# TPM2_0.net
KiCad netlist of a schematic drawn in EAGLE
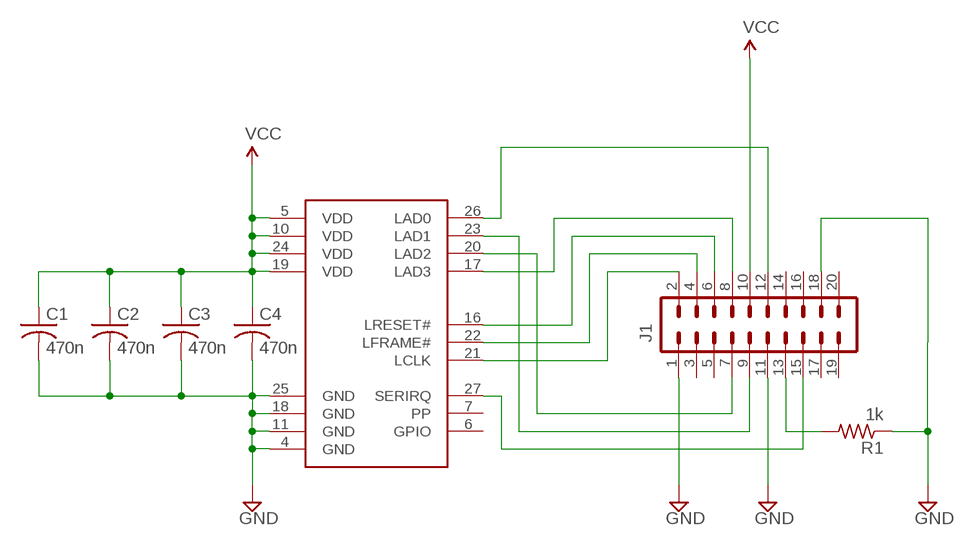
[diagram p0: schematic, sheet 1]

(export (version "E")
  (design (tool "Eeschema 10.0.6"))
  (components
    (comp (ref "C1")
      (value "470n")
      (footprint "eagle-import:C0805K")
      (libsource (lib "eagle-import") (part "C-USC0805K"))
    )
    (comp (ref "C2")
      (value "470n")
      (footprint "eagle-import:C0805K")
      (libsource (lib "eagle-import") (part "C-USC0805K"))
    )
    (comp (ref "C3")
      (value "470n")
      (footprint "eagle-import:C0805K")
      (libsource (lib "eagle-import") (part "C-USC0805K"))
    )
    (comp (ref "C4")
      (value "470n")
      (footprint "eagle-import:C0805K")
      (libsource (lib "eagle-import") (part "C-USC0805K"))
    )
    (comp (ref "J1")
      (value "M10X22X10_LOCK")
      (footprint "eagle-import:2X10_LOCK")
      (libsource (lib "eagle-import") (part "M10X22X10_LOCK"))
    )
    (comp (ref "R1")
      (value "1k")
      (footprint "eagle-import:R0805")
      (libsource (lib "eagle-import") (part "R-US_R0805"))
    )
    (comp (ref "U$1")
      (value "SLB9965")
      (footprint "eagle-import:INF-PG-TSSOP-28-16_M_1PRIMARY")
      (libsource (lib "eagle-import") (part "SLB9965"))
    )
  )
  (nets
    (net (code "1") (name "GND") (class "Default")
      (node (ref "C1") (pin "2") (pinfunction "2_2") (pintype "passive"))
      (node (ref "C2") (pin "2") (pinfunction "2_2") (pintype "passive"))
      (node (ref "C3") (pin "2") (pinfunction "2_2") (pintype "passive"))
      (node (ref "C4") (pin "2") (pinfunction "2_2") (pintype "passive"))
      (node (ref "J1") (pin "1") (pinfunction "1_1") (pintype "passive"))
      (node (ref "J1") (pin "11") (pinfunction "11_11") (pintype "passive"))
      (node (ref "J1") (pin "18") (pinfunction "18_18") (pintype "passive"))
      (node (ref "R1") (pin "1") (pinfunction "1_1") (pintype "passive"))
      (node (ref "U$1") (pin "11") (pinfunction "GND_11") (pintype "power_in"))
      (node (ref "U$1") (pin "18") (pinfunction "GND_18") (pintype "power_in"))
      (node (ref "U$1") (pin "25") (pinfunction "GND_25") (pintype "power_in"))
      (node (ref "U$1") (pin "4") (pinfunction "GND_4") (pintype "power_in"))
    )
    (net (code "2") (name "Net-(J1-Pad13)") (class "Default")
      (node (ref "J1") (pin "13") (pinfunction "13_13") (pintype "passive"))
      (node (ref "R1") (pin "2") (pinfunction "2_2") (pintype "passive"))
    )
    (net (code "3") (name "Net-(U$1-LAD0)") (class "Default")
      (node (ref "J1") (pin "12") (pinfunction "12_12") (pintype "passive"))
      (node (ref "U$1") (pin "26") (pinfunction "LAD0_26") (pintype "bidirectional"))
    )
    (net (code "4") (name "Net-(U$1-LAD1)") (class "Default")
      (node (ref "J1") (pin "9") (pinfunction "9_9") (pintype "passive"))
      (node (ref "U$1") (pin "23") (pinfunction "LAD1_23") (pintype "bidirectional"))
    )
    (net (code "5") (name "Net-(U$1-LAD2)") (class "Default")
      (node (ref "J1") (pin "7") (pinfunction "7_7") (pintype "passive"))
      (node (ref "U$1") (pin "20") (pinfunction "LAD2_20") (pintype "bidirectional"))
    )
    (net (code "6") (name "Net-(U$1-LAD3)") (class "Default")
      (node (ref "J1") (pin "8") (pinfunction "8_8") (pintype "passive"))
      (node (ref "U$1") (pin "17") (pinfunction "LAD3_17") (pintype "bidirectional"))
    )
    (net (code "7") (name "Net-(U$1-LCLK)") (class "Default")
      (node (ref "J1") (pin "2") (pinfunction "2_2") (pintype "passive"))
      (node (ref "U$1") (pin "21") (pinfunction "LCLK_21") (pintype "bidirectional"))
    )
    (net (code "8") (name "Net-(U$1-LFRAME#)") (class "Default")
      (node (ref "J1") (pin "4") (pinfunction "4_4") (pintype "passive"))
      (node (ref "U$1") (pin "22") (pinfunction "LFRAME#_22") (pintype "bidirectional"))
    )
    (net (code "9") (name "Net-(U$1-LRESET#)") (class "Default")
      (node (ref "J1") (pin "6") (pinfunction "6_6") (pintype "passive"))
      (node (ref "U$1") (pin "16") (pinfunction "LRESET#_16") (pintype "bidirectional"))
    )
    (net (code "10") (name "Net-(U$1-SERIRQ)") (class "Default")
      (node (ref "J1") (pin "15") (pinfunction "15_15") (pintype "passive"))
      (node (ref "U$1") (pin "27") (pinfunction "SERIRQ_27") (pintype "bidirectional"))
    )
    (net (code "11") (name "VCC") (class "Default")
      (node (ref "C1") (pin "1") (pinfunction "1_1") (pintype "passive"))
      (node (ref "C2") (pin "1") (pinfunction "1_1") (pintype "passive"))
      (node (ref "C3") (pin "1") (pinfunction "1_1") (pintype "passive"))
      (node (ref "C4") (pin "1") (pinfunction "1_1") (pintype "passive"))
      (node (ref "J1") (pin "10") (pinfunction "10_10") (pintype "passive"))
      (node (ref "U$1") (pin "10") (pinfunction "VDD_10") (pintype "power_in"))
      (node (ref "U$1") (pin "19") (pinfunction "VDD_19") (pintype "power_in"))
      (node (ref "U$1") (pin "24") (pinfunction "VDD_24") (pintype "power_in"))
      (node (ref "U$1") (pin "5") (pinfunction "VDD_5") (pintype "power_in"))
    )
    (net (code "12") (name "unconnected-(J1-Pad3)") (class "Default")
      (node (ref "J1") (pin "3") (pinfunction "3_3") (pintype "passive"))
    )
    (net (code "13") (name "unconnected-(J1-Pad5)") (class "Default")
      (node (ref "J1") (pin "5") (pinfunction "5_5") (pintype "passive"))
    )
    (net (code "14") (name "unconnected-(J1-Pad14)") (class "Default")
      (node (ref "J1") (pin "14") (pinfunction "14_14") (pintype "passive"))
    )
    (net (code "15") (name "unconnected-(J1-Pad16)") (class "Default")
      (node (ref "J1") (pin "16") (pinfunction "16_16") (pintype "passive"))
    )
    (net (code "16") (name "unconnected-(J1-Pad17)") (class "Default")
      (node (ref "J1") (pin "17") (pinfunction "17_17") (pintype "passive"))
    )
    (net (code "17") (name "unconnected-(J1-Pad19)") (class "Default")
      (node (ref "J1") (pin "19") (pinfunction "19_19") (pintype "passive"))
    )
    (net (code "18") (name "unconnected-(J1-Pad20)") (class "Default")
      (node (ref "J1") (pin "20") (pinfunction "20_20") (pintype "passive"))
    )
    (net (code "19") (name "unconnected-(U$1-GPIO-Pad6)") (class "Default")
      (node (ref "U$1") (pin "6") (pinfunction "GPIO_6") (pintype "bidirectional"))
    )
    (net (code "20") (name "unconnected-(U$1-PP-Pad7)") (class "Default")
      (node (ref "U$1") (pin "7") (pinfunction "PP_7") (pintype "bidirectional"))
    )
  )
)
